# LED_Array.net
KiCad netlist of a schematic drawn in Altium Designer
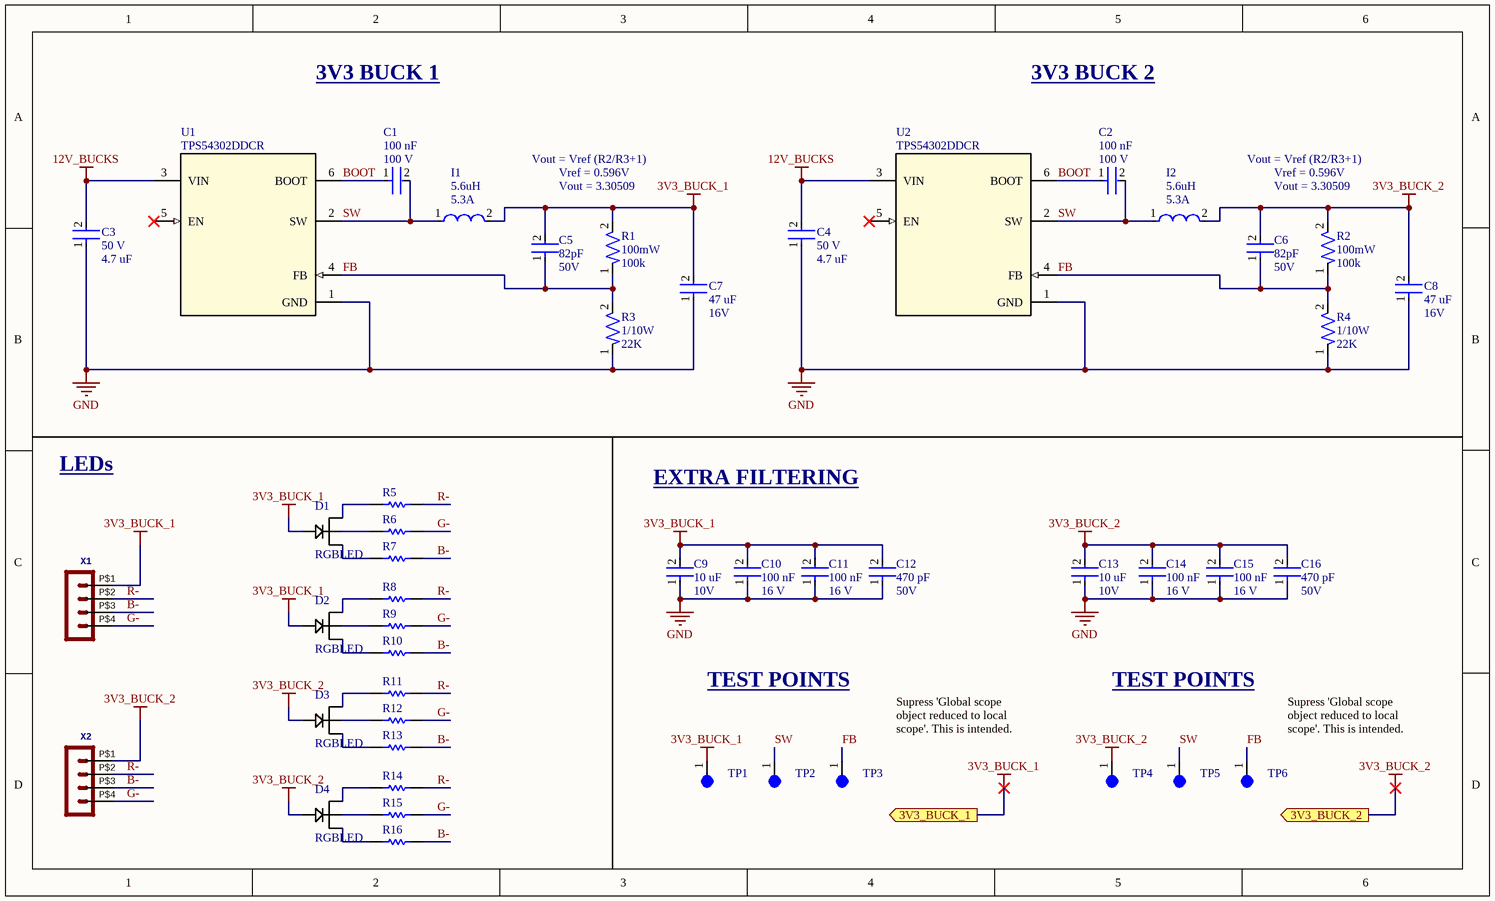
[diagram p0: LED_Array.SchDoc]

(export (version "E")
  (design (tool "Eeschema 10.0.6"))
  (components
    (comp (ref "C1")
      (value "CC0603KRX7R0BB104")
      (footprint "CAP-0603")
      (description "CAP CER 0.1UF 100V X7R 0603")
      (fields (field (name "CAPACITANCE") "100 nF") (field (name "VOLTAGE") "100 V"))
      (libsource (lib "JLC_25") (part "CAP-100N-0001"))
    )
    (comp (ref "C2")
      (value "CC0603KRX7R0BB104")
      (footprint "CAP-0603")
      (description "CAP CER 0.1UF 100V X7R 0603")
      (fields (field (name "CAPACITANCE") "100 nF") (field (name "VOLTAGE") "100 V"))
      (libsource (lib "JLC_25") (part "CAP-100N-0001"))
    )
    (comp (ref "C3")
      (value "CC0805KKX5R9BB475")
      (footprint "CAP-0805")
      (description "CAP CER 4.7UF 50V X5R 0805")
      (fields (field (name "VOLTAGE") "50 V") (field (name "CAPACITANCE") "4.7 uF"))
      (libsource (lib "JLC_25") (part "CAP-4.7U-0002"))
    )
    (comp (ref "C4")
      (value "CC0805KKX5R9BB475")
      (footprint "CAP-0805")
      (description "CAP CER 4.7UF 50V X5R 0805")
      (fields (field (name "VOLTAGE") "50 V") (field (name "CAPACITANCE") "4.7 uF"))
      (libsource (lib "JLC_25") (part "CAP-4.7U-0002"))
    )
    (comp (ref "C5")
      (value "CC0805JRNPO9BN820")
      (footprint "CAP-0805")
      (description "82 pF ±5% 50V Ceramic Capacitor C0G, NP0 0805 (2012 Metric)")
      (fields (field (name "VOLTAGE") "50V") (field (name "CAPACITANCE") "82pF"))
      (libsource (lib "JLC_25") (part "CAP-82P-0001"))
    )
    (comp (ref "C6")
      (value "CC0805JRNPO9BN820")
      (footprint "CAP-0805")
      (description "82 pF ±5% 50V Ceramic Capacitor C0G, NP0 0805 (2012 Metric)")
      (fields (field (name "VOLTAGE") "50V") (field (name "CAPACITANCE") "82pF"))
      (libsource (lib "JLC_25") (part "CAP-82P-0001"))
    )
    (comp (ref "C7")
      (value "GRM32ER61C476KE15L")
      (footprint "CAP-1210")
      (description "CAP CER 47UF 16V X5R 1210")
      (fields (field (name "CAPACITANCE") "47 uF") (field (name "VOLTAGE") "16V"))
      (libsource (lib "JLC_25") (part "CAP-47U-0002"))
    )
    (comp (ref "C8")
      (value "GRM32ER61C476KE15L")
      (footprint "CAP-1210")
      (description "CAP CER 47UF 16V X5R 1210")
      (fields (field (name "CAPACITANCE") "47 uF") (field (name "VOLTAGE") "16V"))
      (libsource (lib "JLC_25") (part "CAP-47U-0002"))
    )
    (comp (ref "C9")
      (value "CC0603KRX5R6BB106")
      (footprint "CAP-0603")
      (description "CAP CER 10UF 10V X5R 0603")
      (fields (field (name "VOLTAGE") "10V") (field (name "CAPACITANCE") "10 uF"))
      (libsource (lib "JLC_25") (part "CAP-10U-0001"))
    )
    (comp (ref "C10")
      (value "CC0402KRX7R7BB104")
      (footprint "CAP-0402")
      (description "CAP CER 0.1UF 16V X7R 0402")
      (fields (field (name "VOLTAGE RATING") "16 V") (field (name "CAPACITANCE") "100 nF"))
      (libsource (lib "JLC_25") (part "CAP-0.1U-0001"))
    )
    (comp (ref "C11")
      (value "CC0402KRX7R7BB104")
      (footprint "CAP-0402")
      (description "CAP CER 0.1UF 16V X7R 0402")
      (fields (field (name "VOLTAGE RATING") "16 V") (field (name "CAPACITANCE") "100 nF"))
      (libsource (lib "JLC_25") (part "CAP-0.1U-0001"))
    )
    (comp (ref "C12")
      (value "CC0805JRNPO9BN471")
      (footprint "CAP-0805")
      (description "CAP CER 470PF 50V C0G/NPO 0805")
      (fields (field (name "VOLTAGE") "50V") (field (name "CAPACITANCE") "470 pF"))
      (libsource (lib "JLC_25") (part "CAP-470P-0001"))
    )
    (comp (ref "C13")
      (value "CC0603KRX5R6BB106")
      (footprint "CAP-0603")
      (description "CAP CER 10UF 10V X5R 0603")
      (fields (field (name "VOLTAGE") "10V") (field (name "CAPACITANCE") "10 uF"))
      (libsource (lib "JLC_25") (part "CAP-10U-0001"))
    )
    (comp (ref "C14")
      (value "CC0402KRX7R7BB104")
      (footprint "CAP-0402")
      (description "CAP CER 0.1UF 16V X7R 0402")
      (fields (field (name "VOLTAGE RATING") "16 V") (field (name "CAPACITANCE") "100 nF"))
      (libsource (lib "JLC_25") (part "CAP-0.1U-0001"))
    )
    (comp (ref "C15")
      (value "CC0402KRX7R7BB104")
      (footprint "CAP-0402")
      (description "CAP CER 0.1UF 16V X7R 0402")
      (fields (field (name "VOLTAGE RATING") "16 V") (field (name "CAPACITANCE") "100 nF"))
      (libsource (lib "JLC_25") (part "CAP-0.1U-0001"))
    )
    (comp (ref "C16")
      (value "CC0805JRNPO9BN471")
      (footprint "CAP-0805")
      (description "CAP CER 470PF 50V C0G/NPO 0805")
      (fields (field (name "VOLTAGE") "50V") (field (name "CAPACITANCE") "470 pF"))
      (libsource (lib "JLC_25") (part "CAP-470P-0001"))
    )
    (comp (ref "D1")
      (value "RGBLED")
      (footprint "RGBLED")
      (libsource (lib "RoverTransistors") (part "RGBLED"))
    )
    (comp (ref "D2")
      (value "RGBLED")
      (footprint "RGBLED")
      (libsource (lib "RoverTransistors") (part "RGBLED"))
    )
    (comp (ref "D3")
      (value "RGBLED")
      (footprint "RGBLED")
      (libsource (lib "RoverTransistors") (part "RGBLED"))
    )
    (comp (ref "D4")
      (value "RGBLED")
      (footprint "RGBLED")
      (libsource (lib "RoverTransistors") (part "RGBLED"))
    )
    (comp (ref "I1")
      (value "ASPI-1306T-5R6M-T")
      (footprint "IND-5.6UH-0001")
      (description "5.6 µH Unshielded Drum Core, Wirewound Inductor 5.3 A 20mOhm Max Nonstandard")
      (fields (field (name "SATURATION CURRENT") "5.3A") (field (name "INDUCTANCE") "5.6uH"))
      (libsource (lib "JLC_25") (part "IND-5.6U-0001"))
    )
    (comp (ref "I2")
      (value "ASPI-1306T-5R6M-T")
      (footprint "IND-5.6UH-0001")
      (description "5.6 µH Unshielded Drum Core, Wirewound Inductor 5.3 A 20mOhm Max Nonstandard")
      (fields (field (name "SATURATION CURRENT") "5.3A") (field (name "INDUCTANCE") "5.6uH"))
      (libsource (lib "JLC_25") (part "IND-5.6U-0001"))
    )
    (comp (ref "R1")
      (value "RC0603FR-07100KL")
      (footprint "RES-0603")
      (description "RES SMD 100K OHM 1% 1/10W 0603")
      (fields
        (field (name "TOLERANCE") "1%")
        (field (name "POWER") "100mW")
        (field (name "RESISTANCE") "100k")
      )
      (libsource (lib "JLC_25") (part "RES-100k-0001"))
    )
    (comp (ref "R2")
      (value "RC0603FR-07100KL")
      (footprint "RES-0603")
      (description "RES SMD 100K OHM 1% 1/10W 0603")
      (fields
        (field (name "TOLERANCE") "1%")
        (field (name "POWER") "100mW")
        (field (name "RESISTANCE") "100k")
      )
      (libsource (lib "JLC_25") (part "RES-100k-0001"))
    )
    (comp (ref "R3")
      (value "RC0603FR-0722KL")
      (footprint "RES-0603")
      (description "22 kOhms ±1% 0.1W, 1/10W Chip Resistor 0603 (1608 Metric) Moisture Resistant Thick Film")
      (fields (field (name "POWER") "1/10W") (field (name "RESISTANCE") "22K"))
      (libsource (lib "JLC_25") (part "RES-22k-0001"))
    )
    (comp (ref "R4")
      (value "RC0603FR-0722KL")
      (footprint "RES-0603")
      (description "22 kOhms ±1% 0.1W, 1/10W Chip Resistor 0603 (1608 Metric) Moisture Resistant Thick Film")
      (fields (field (name "POWER") "1/10W") (field (name "RESISTANCE") "22K"))
      (libsource (lib "JLC_25") (part "RES-22k-0001"))
    )
    (comp (ref "R5")
      (value "Res1")
      (footprint "AXIAL-0.3")
      (description "Resistor")
      (fields (field (name "PUBLISHER") "Altium Limited"))
      (libsource (lib "Miscellaneous Devices") (part "Res1"))
    )
    (comp (ref "R6")
      (value "Res1")
      (footprint "AXIAL-0.3")
      (description "Resistor")
      (fields (field (name "PUBLISHER") "Altium Limited"))
      (libsource (lib "Miscellaneous Devices") (part "Res1"))
    )
    (comp (ref "R7")
      (value "Res1")
      (footprint "AXIAL-0.3")
      (description "Resistor")
      (fields (field (name "PUBLISHER") "Altium Limited"))
      (libsource (lib "Miscellaneous Devices") (part "Res1"))
    )
    (comp (ref "R8")
      (value "Res1")
      (footprint "AXIAL-0.3")
      (description "Resistor")
      (fields (field (name "PUBLISHER") "Altium Limited"))
      (libsource (lib "Miscellaneous Devices") (part "Res1"))
    )
    (comp (ref "R9")
      (value "Res1")
      (footprint "AXIAL-0.3")
      (description "Resistor")
      (fields (field (name "PUBLISHER") "Altium Limited"))
      (libsource (lib "Miscellaneous Devices") (part "Res1"))
    )
    (comp (ref "R10")
      (value "Res1")
      (footprint "AXIAL-0.3")
      (description "Resistor")
      (fields (field (name "PUBLISHER") "Altium Limited"))
      (libsource (lib "Miscellaneous Devices") (part "Res1"))
    )
    (comp (ref "R11")
      (value "Res1")
      (footprint "AXIAL-0.3")
      (description "Resistor")
      (fields (field (name "PUBLISHER") "Altium Limited"))
      (libsource (lib "Miscellaneous Devices") (part "Res1"))
    )
    (comp (ref "R12")
      (value "Res1")
      (footprint "AXIAL-0.3")
      (description "Resistor")
      (fields (field (name "PUBLISHER") "Altium Limited"))
      (libsource (lib "Miscellaneous Devices") (part "Res1"))
    )
    (comp (ref "R13")
      (value "Res1")
      (footprint "AXIAL-0.3")
      (description "Resistor")
      (fields (field (name "PUBLISHER") "Altium Limited"))
      (libsource (lib "Miscellaneous Devices") (part "Res1"))
    )
    (comp (ref "R14")
      (value "Res1")
      (footprint "AXIAL-0.3")
      (description "Resistor")
      (fields (field (name "PUBLISHER") "Altium Limited"))
      (libsource (lib "Miscellaneous Devices") (part "Res1"))
    )
    (comp (ref "R15")
      (value "Res1")
      (footprint "AXIAL-0.3")
      (description "Resistor")
      (fields (field (name "PUBLISHER") "Altium Limited"))
      (libsource (lib "Miscellaneous Devices") (part "Res1"))
    )
    (comp (ref "R16")
      (value "Res1")
      (footprint "AXIAL-0.3")
      (description "Resistor")
      (fields (field (name "PUBLISHER") "Altium Limited"))
      (libsource (lib "Miscellaneous Devices") (part "Res1"))
    )
    (comp (ref "TP1")
      (value "5003")
      (footprint "TEST-POINT-0001")
      (description "Oranange PC Test Point, Miniature Phoisphor Bronze Silver Plating Through Hole Mounting Type")
      (libsource (lib "*") (part "TEST-POINT-0001"))
    )
    (comp (ref "TP2")
      (value "5003")
      (footprint "TEST-POINT-0001")
      (description "Oranange PC Test Point, Miniature Phoisphor Bronze Silver Plating Through Hole Mounting Type")
      (libsource (lib "*") (part "TEST-POINT-0001"))
    )
    (comp (ref "TP3")
      (value "5003")
      (footprint "TEST-POINT-0001")
      (description "Oranange PC Test Point, Miniature Phoisphor Bronze Silver Plating Through Hole Mounting Type")
      (libsource (lib "*") (part "TEST-POINT-0001"))
    )
    (comp (ref "TP4")
      (value "5003")
      (footprint "TEST-POINT-0001")
      (description "Oranange PC Test Point, Miniature Phoisphor Bronze Silver Plating Through Hole Mounting Type")
      (libsource (lib "*") (part "TEST-POINT-0001"))
    )
    (comp (ref "TP5")
      (value "5003")
      (footprint "TEST-POINT-0001")
      (description "Oranange PC Test Point, Miniature Phoisphor Bronze Silver Plating Through Hole Mounting Type")
      (libsource (lib "*") (part "TEST-POINT-0001"))
    )
    (comp (ref "TP6")
      (value "5003")
      (footprint "TEST-POINT-0001")
      (description "Oranange PC Test Point, Miniature Phoisphor Bronze Silver Plating Through Hole Mounting Type")
      (libsource (lib "*") (part "TEST-POINT-0001"))
    )
    (comp (ref "U1")
      (value "TPS54302DDCR")
      (footprint "IC-SOT-23-6")
      (description "IC REG BUCK ADJ 3A SOT23")
      (libsource (lib "JLC_25") (part "IC-BUCK-0004"))
    )
    (comp (ref "U2")
      (value "TPS54302DDCR")
      (footprint "IC-SOT-23-6")
      (description "IC REG BUCK ADJ 3A SOT23")
      (libsource (lib "JLC_25") (part "IC-BUCK-0004"))
    )
    (comp (ref "X1")
      (value "Molex - Micro-Fit 3.0 Series connector,  3.00mm (0.118\") pitch header, 4 positions.")
      (footprint "43650-0400")
      (libsource (lib "Molex Microfit") (part "HEADER_POS4_?43650-0400"))
    )
    (comp (ref "X2")
      (value "Molex - Micro-Fit 3.0 Series connector,  3.00mm (0.118\") pitch header, 4 positions.")
      (footprint "43650-0400")
      (libsource (lib "Molex Microfit") (part "HEADER_POS4_?43650-0400"))
    )
  )
  (nets
    (net (code "1") (name "/B-") (class "Default")
      (node (ref "R10") (pin "2") (pinfunction "2_2") (pintype "passive"))
      (node (ref "R13") (pin "2") (pinfunction "2_2") (pintype "passive"))
      (node (ref "R16") (pin "2") (pinfunction "2_2") (pintype "passive"))
      (node (ref "R7") (pin "2") (pinfunction "2_2") (pintype "passive"))
      (node (ref "X1") (pin "P$3") (pinfunction "3_P$3") (pintype "passive"))
      (node (ref "X2") (pin "P$3") (pinfunction "3_P$3") (pintype "passive"))
    )
    (net (code "2") (name "/BOOT") (class "Default")
      (node (ref "C1") (pin "1") (pinfunction "1_1") (pintype "passive"))
      (node (ref "C2") (pin "1") (pinfunction "1_1") (pintype "passive"))
      (node (ref "U1") (pin "6") (pinfunction "BOOT_6") (pintype "power_in"))
      (node (ref "U2") (pin "6") (pinfunction "BOOT_6") (pintype "power_in"))
    )
    (net (code "3") (name "/FB") (class "Default")
      (node (ref "C5") (pin "1") (pinfunction "1_1") (pintype "passive"))
      (node (ref "C6") (pin "1") (pinfunction "1_1") (pintype "passive"))
      (node (ref "R1") (pin "1") (pinfunction "1_1") (pintype "passive"))
      (node (ref "R2") (pin "1") (pinfunction "1_1") (pintype "passive"))
      (node (ref "R3") (pin "2") (pinfunction "2_2") (pintype "passive"))
      (node (ref "R4") (pin "2") (pinfunction "2_2") (pintype "passive"))
      (node (ref "TP3") (pin "1") (pinfunction "0_1") (pintype "passive"))
      (node (ref "TP6") (pin "1") (pinfunction "0_1") (pintype "passive"))
      (node (ref "U1") (pin "4") (pinfunction "FB_4") (pintype "input"))
      (node (ref "U2") (pin "4") (pinfunction "FB_4") (pintype "input"))
    )
    (net (code "4") (name "/G-") (class "Default")
      (node (ref "R12") (pin "2") (pinfunction "2_2") (pintype "passive"))
      (node (ref "R15") (pin "2") (pinfunction "2_2") (pintype "passive"))
      (node (ref "R6") (pin "2") (pinfunction "2_2") (pintype "passive"))
      (node (ref "R9") (pin "2") (pinfunction "2_2") (pintype "passive"))
      (node (ref "X1") (pin "P$4") (pinfunction "4_P$4") (pintype "passive"))
      (node (ref "X2") (pin "P$4") (pinfunction "4_P$4") (pintype "passive"))
    )
    (net (code "5") (name "/R-") (class "Default")
      (node (ref "R11") (pin "2") (pinfunction "2_2") (pintype "passive"))
      (node (ref "R14") (pin "2") (pinfunction "2_2") (pintype "passive"))
      (node (ref "R5") (pin "2") (pinfunction "2_2") (pintype "passive"))
      (node (ref "R8") (pin "2") (pinfunction "2_2") (pintype "passive"))
      (node (ref "X1") (pin "P$2") (pinfunction "1_P$2") (pintype "passive"))
      (node (ref "X2") (pin "P$2") (pinfunction "1_P$2") (pintype "passive"))
    )
    (net (code "6") (name "/SW") (class "Default")
      (node (ref "C1") (pin "2") (pinfunction "2_2") (pintype "passive"))
      (node (ref "C2") (pin "2") (pinfunction "2_2") (pintype "passive"))
      (node (ref "I1") (pin "1") (pinfunction "1_1") (pintype "passive"))
      (node (ref "I2") (pin "1") (pinfunction "1_1") (pintype "passive"))
      (node (ref "TP2") (pin "1") (pinfunction "0_1") (pintype "passive"))
      (node (ref "TP5") (pin "1") (pinfunction "0_1") (pintype "passive"))
      (node (ref "U1") (pin "2") (pinfunction "SW_2") (pintype "power_in"))
      (node (ref "U2") (pin "2") (pinfunction "SW_2") (pintype "power_in"))
    )
    (net (code "7") (name "3V3_BUCK_1") (class "Default")
      (node (ref "C10") (pin "2") (pinfunction "2_2") (pintype "passive"))
      (node (ref "C11") (pin "2") (pinfunction "2_2") (pintype "passive"))
      (node (ref "C12") (pin "2") (pinfunction "2_2") (pintype "passive"))
      (node (ref "C5") (pin "2") (pinfunction "2_2") (pintype "passive"))
      (node (ref "C7") (pin "2") (pinfunction "2_2") (pintype "passive"))
      (node (ref "C9") (pin "2") (pinfunction "2_2") (pintype "passive"))
      (node (ref "D1") (pin "0") (pinfunction "7_0") (pintype "passive"))
      (node (ref "D2") (pin "0") (pinfunction "7_0") (pintype "passive"))
      (node (ref "I1") (pin "2") (pinfunction "2_2") (pintype "passive"))
      (node (ref "R1") (pin "2") (pinfunction "2_2") (pintype "passive"))
      (node (ref "TP1") (pin "1") (pinfunction "0_1") (pintype "passive"))
      (node (ref "X1") (pin "P$1") (pinfunction "2_P$1") (pintype "passive"))
    )
    (net (code "8") (name "3V3_BUCK_2") (class "Default")
      (node (ref "C13") (pin "2") (pinfunction "2_2") (pintype "passive"))
      (node (ref "C14") (pin "2") (pinfunction "2_2") (pintype "passive"))
      (node (ref "C15") (pin "2") (pinfunction "2_2") (pintype "passive"))
      (node (ref "C16") (pin "2") (pinfunction "2_2") (pintype "passive"))
      (node (ref "C6") (pin "2") (pinfunction "2_2") (pintype "passive"))
      (node (ref "C8") (pin "2") (pinfunction "2_2") (pintype "passive"))
      (node (ref "D3") (pin "0") (pinfunction "7_0") (pintype "passive"))
      (node (ref "D4") (pin "0") (pinfunction "7_0") (pintype "passive"))
      (node (ref "I2") (pin "2") (pinfunction "2_2") (pintype "passive"))
      (node (ref "R2") (pin "2") (pinfunction "2_2") (pintype "passive"))
      (node (ref "TP4") (pin "1") (pinfunction "0_1") (pintype "passive"))
      (node (ref "X2") (pin "P$1") (pinfunction "2_P$1") (pintype "passive"))
    )
    (net (code "9") (name "12V_BUCKS") (class "Default")
      (node (ref "C3") (pin "2") (pinfunction "2_2") (pintype "passive"))
      (node (ref "C4") (pin "2") (pinfunction "2_2") (pintype "passive"))
      (node (ref "U1") (pin "3") (pinfunction "VIN_3") (pintype "power_in"))
      (node (ref "U2") (pin "3") (pinfunction "VIN_3") (pintype "power_in"))
    )
    (net (code "10") (name "GND") (class "Default")
      (node (ref "C10") (pin "1") (pinfunction "1_1") (pintype "passive"))
      (node (ref "C11") (pin "1") (pinfunction "1_1") (pintype "passive"))
      (node (ref "C12") (pin "1") (pinfunction "1_1") (pintype "passive"))
      (node (ref "C13") (pin "1") (pinfunction "1_1") (pintype "passive"))
      (node (ref "C14") (pin "1") (pinfunction "1_1") (pintype "passive"))
      (node (ref "C15") (pin "1") (pinfunction "1_1") (pintype "passive"))
      (node (ref "C16") (pin "1") (pinfunction "1_1") (pintype "passive"))
      (node (ref "C3") (pin "1") (pinfunction "1_1") (pintype "passive"))
      (node (ref "C4") (pin "1") (pinfunction "1_1") (pintype "passive"))
      (node (ref "C7") (pin "1") (pinfunction "1_1") (pintype "passive"))
      (node (ref "C8") (pin "1") (pinfunction "1_1") (pintype "passive"))
      (node (ref "C9") (pin "1") (pinfunction "1_1") (pintype "passive"))
      (node (ref "R3") (pin "1") (pinfunction "1_1") (pintype "passive"))
      (node (ref "R4") (pin "1") (pinfunction "1_1") (pintype "passive"))
      (node (ref "U1") (pin "1") (pinfunction "GND_1") (pintype "power_in"))
      (node (ref "U2") (pin "1") (pinfunction "GND_1") (pintype "power_in"))
    )
    (net (code "11") (name "Net-(D1-B-)") (class "Default")
      (node (ref "D1") (pin "3") (pinfunction "B-_3") (pintype "passive"))
      (node (ref "R7") (pin "1") (pinfunction "1_1") (pintype "passive"))
    )
    (net (code "12") (name "Net-(D1-G-)") (class "Default")
      (node (ref "D1") (pin "2") (pinfunction "G-_2") (pintype "passive"))
      (node (ref "R6") (pin "1") (pinfunction "1_1") (pintype "passive"))
    )
    (net (code "13") (name "Net-(D1-R-)") (class "Default")
      (node (ref "D1") (pin "1") (pinfunction "R-_1") (pintype "passive"))
      (node (ref "R5") (pin "1") (pinfunction "1_1") (pintype "passive"))
    )
    (net (code "14") (name "Net-(D2-B-)") (class "Default")
      (node (ref "D2") (pin "3") (pinfunction "B-_3") (pintype "passive"))
      (node (ref "R10") (pin "1") (pinfunction "1_1") (pintype "passive"))
    )
    (net (code "15") (name "Net-(D2-G-)") (class "Default")
      (node (ref "D2") (pin "2") (pinfunction "G-_2") (pintype "passive"))
      (node (ref "R9") (pin "1") (pinfunction "1_1") (pintype "passive"))
    )
    (net (code "16") (name "Net-(D2-R-)") (class "Default")
      (node (ref "D2") (pin "1") (pinfunction "R-_1") (pintype "passive"))
      (node (ref "R8") (pin "1") (pinfunction "1_1") (pintype "passive"))
    )
    (net (code "17") (name "Net-(D3-B-)") (class "Default")
      (node (ref "D3") (pin "3") (pinfunction "B-_3") (pintype "passive"))
      (node (ref "R13") (pin "1") (pinfunction "1_1") (pintype "passive"))
    )
    (net (code "18") (name "Net-(D3-G-)") (class "Default")
      (node (ref "D3") (pin "2") (pinfunction "G-_2") (pintype "passive"))
      (node (ref "R12") (pin "1") (pinfunction "1_1") (pintype "passive"))
    )
    (net (code "19") (name "Net-(D3-R-)") (class "Default")
      (node (ref "D3") (pin "1") (pinfunction "R-_1") (pintype "passive"))
      (node (ref "R11") (pin "1") (pinfunction "1_1") (pintype "passive"))
    )
    (net (code "20") (name "Net-(D4-B-)") (class "Default")
      (node (ref "D4") (pin "3") (pinfunction "B-_3") (pintype "passive"))
      (node (ref "R16") (pin "1") (pinfunction "1_1") (pintype "passive"))
    )
    (net (code "21") (name "Net-(D4-G-)") (class "Default")
      (node (ref "D4") (pin "2") (pinfunction "G-_2") (pintype "passive"))
      (node (ref "R15") (pin "1") (pinfunction "1_1") (pintype "passive"))
    )
    (net (code "22") (name "Net-(D4-R-)") (class "Default")
      (node (ref "D4") (pin "1") (pinfunction "R-_1") (pintype "passive"))
      (node (ref "R14") (pin "1") (pinfunction "1_1") (pintype "passive"))
    )
    (net (code "23") (name "unconnected-(U1-EN-Pad5)") (class "Default")
      (node (ref "U1") (pin "5") (pinfunction "EN_5") (pintype "input+no_connect"))
    )
    (net (code "24") (name "unconnected-(U2-EN-Pad5)") (class "Default")
      (node (ref "U2") (pin "5") (pinfunction "EN_5") (pintype "input+no_connect"))
    )
  )
)
